# minutka_hlavni.net
KiCad netlist of a schematic drawn in EAGLE
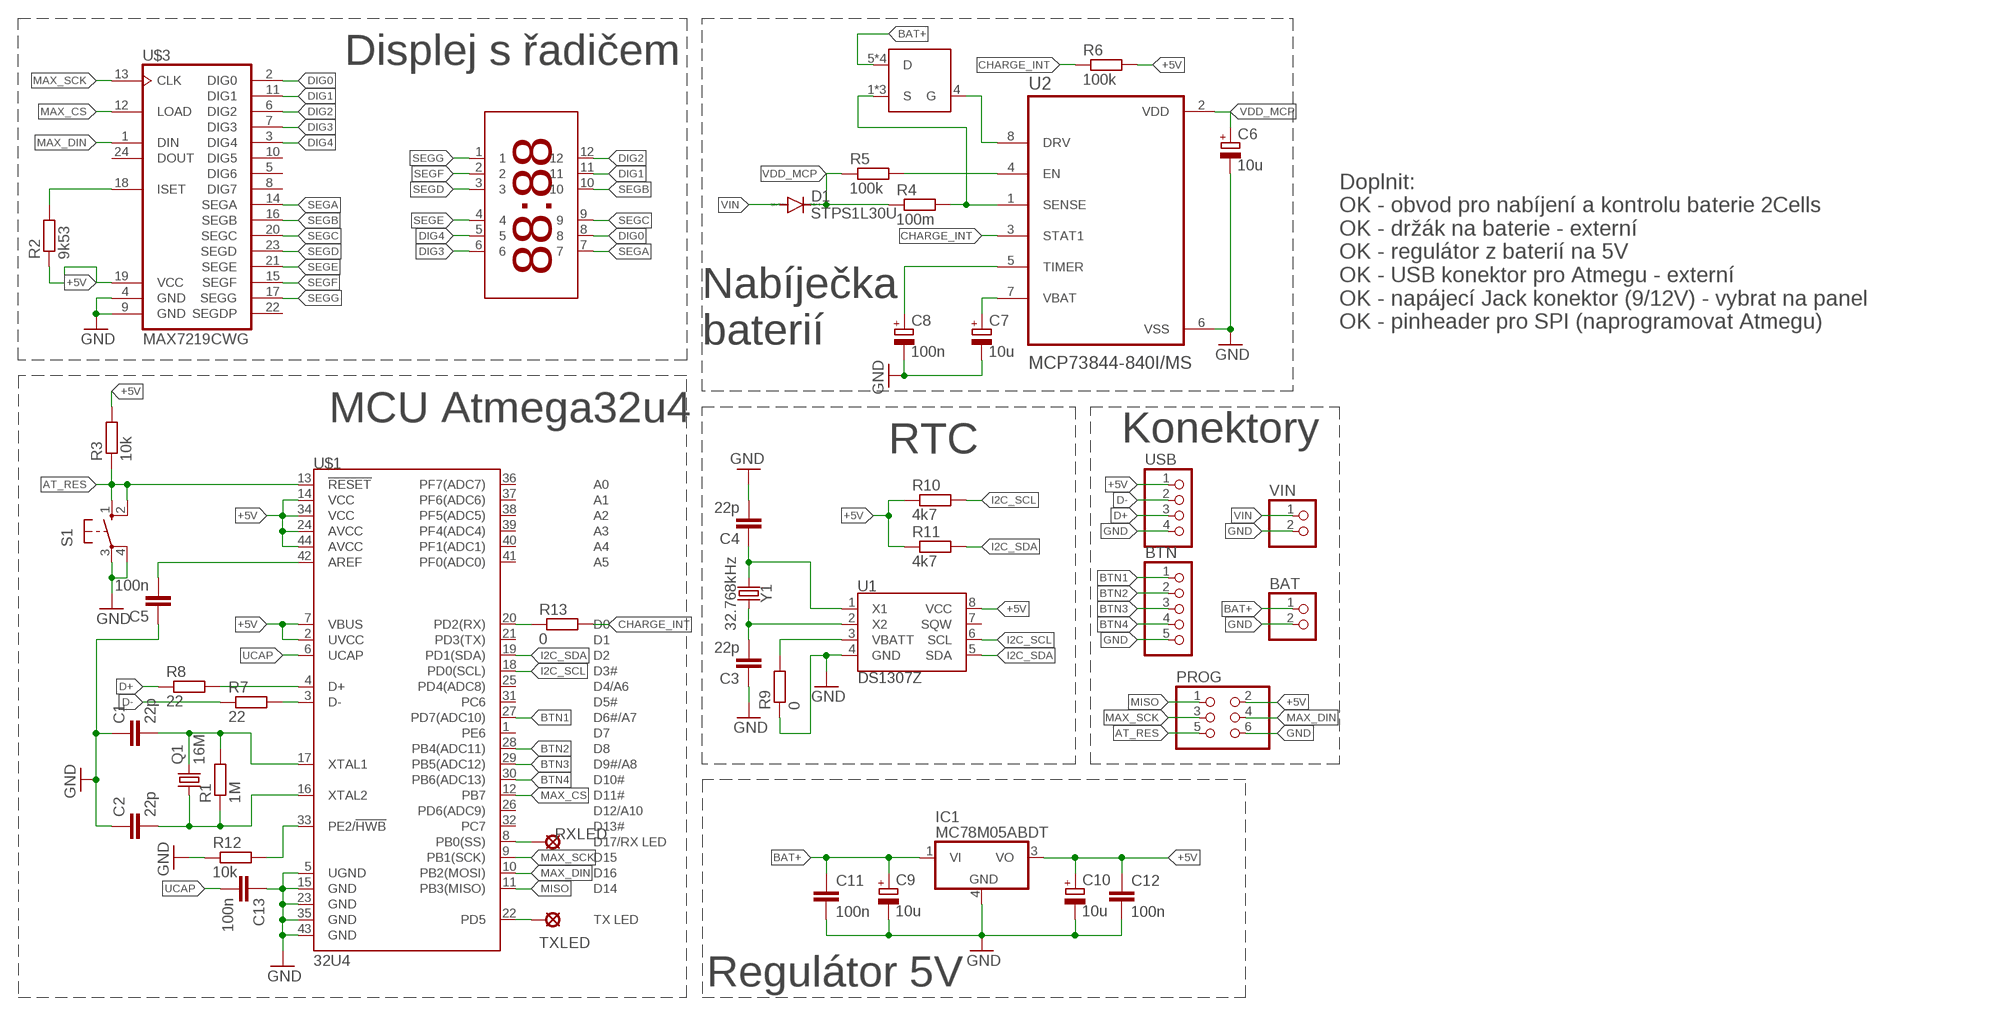
[diagram p0: schematic, sheet 1]

(export (version "E")
  (design (tool "Eeschema 10.0.6"))
  (components
    (comp (ref "BAT")
      (value "PINHD-1X2")
      (footprint "eagle-import:1X02")
      (libsource (lib "eagle-import") (part "PINHD-1X2"))
    )
    (comp (ref "BTN")
      (value "PINHD-1X5")
      (footprint "eagle-import:1X05")
      (libsource (lib "eagle-import") (part "PINHD-1X5"))
    )
    (comp (ref "C1")
      (value "22p")
      (footprint "eagle-import:C0603")
      (libsource (lib "eagle-import") (part "C-EUC0603"))
    )
    (comp (ref "C2")
      (value "22p")
      (footprint "eagle-import:C0603")
      (libsource (lib "eagle-import") (part "C-EUC0603"))
    )
    (comp (ref "C3")
      (value "22p")
      (footprint "eagle-import:C0603")
      (libsource (lib "eagle-import") (part "C-EUC0603"))
    )
    (comp (ref "C4")
      (value "22p")
      (footprint "eagle-import:C0603")
      (libsource (lib "eagle-import") (part "C-EUC0603"))
    )
    (comp (ref "C5")
      (value "100n")
      (footprint "eagle-import:C0603")
      (libsource (lib "eagle-import") (part "C-EUC0603"))
    )
    (comp (ref "C6")
      (value "10u")
      (footprint "eagle-import:085CS_1AR")
      (libsource (lib "eagle-import") (part "CPOL-EU085CS-1AR"))
    )
    (comp (ref "C7")
      (value "10u")
      (footprint "eagle-import:085CS_1AR")
      (libsource (lib "eagle-import") (part "CPOL-EU085CS-1AR"))
    )
    (comp (ref "C8")
      (value "100n")
      (footprint "eagle-import:085CS_1AR")
      (libsource (lib "eagle-import") (part "CPOL-EU085CS-1AR"))
    )
    (comp (ref "C9")
      (value "10u")
      (footprint "eagle-import:085CS_1AR")
      (libsource (lib "eagle-import") (part "CPOL-EU085CS-1AR"))
    )
    (comp (ref "C10")
      (value "10u")
      (footprint "eagle-import:085CS_1AR")
      (libsource (lib "eagle-import") (part "CPOL-EU085CS-1AR"))
    )
    (comp (ref "C11")
      (value "100n")
      (footprint "eagle-import:C0603")
      (libsource (lib "eagle-import") (part "C-EUC0603"))
    )
    (comp (ref "C12")
      (value "100n")
      (footprint "eagle-import:C0603")
      (libsource (lib "eagle-import") (part "C-EUC0603"))
    )
    (comp (ref "C13")
      (value "100n")
      (footprint "eagle-import:C0603")
      (libsource (lib "eagle-import") (part "C-EUC0603"))
    )
    (comp (ref "D1")
      (value "STPS1L30U")
      (footprint "eagle-import:DO214AA")
      (libsource (lib "eagle-import") (part "DIODE-DO214AA"))
    )
    (comp (ref "IC1")
      (value "MC78M05ABDT")
      (footprint "eagle-import:DPACK_3")
      (libsource (lib "eagle-import") (part "MC78M05ABDT"))
    )
    (comp (ref "PROG")
      (value "PINHD-2X3")
      (footprint "eagle-import:2X03")
      (libsource (lib "eagle-import") (part "PINHD-2X3"))
    )
    (comp (ref "Q1")
      (value "16M")
      (footprint "eagle-import:HC49UP")
      (libsource (lib "eagle-import") (part "CRYSTALHC49UP"))
    )
    (comp (ref "R1")
      (value "1M")
      (footprint "eagle-import:R0603")
      (libsource (lib "eagle-import") (part "R-EU_R0603"))
    )
    (comp (ref "R2")
      (value "9k53")
      (footprint "eagle-import:R0603")
      (libsource (lib "eagle-import") (part "R-EU_R0603"))
    )
    (comp (ref "R3")
      (value "10k")
      (footprint "eagle-import:R0603")
      (libsource (lib "eagle-import") (part "R-EU_R0603"))
    )
    (comp (ref "R4")
      (value "100m")
      (footprint "eagle-import:R0603")
      (libsource (lib "eagle-import") (part "R-EU_R0603"))
    )
    (comp (ref "R5")
      (value "100k")
      (footprint "eagle-import:R0603")
      (libsource (lib "eagle-import") (part "R-EU_R0603"))
    )
    (comp (ref "R6")
      (value "100k")
      (footprint "eagle-import:R0603")
      (libsource (lib "eagle-import") (part "R-EU_R0603"))
    )
    (comp (ref "R7")
      (value "22")
      (footprint "eagle-import:R0603")
      (libsource (lib "eagle-import") (part "R-EU_R0603"))
    )
    (comp (ref "R8")
      (value "22")
      (footprint "eagle-import:R0603")
      (libsource (lib "eagle-import") (part "R-EU_R0603"))
    )
    (comp (ref "R9")
      (value "0")
      (footprint "eagle-import:R0603")
      (libsource (lib "eagle-import") (part "R-EU_R0603"))
    )
    (comp (ref "R10")
      (value "4k7")
      (footprint "eagle-import:R0603")
      (libsource (lib "eagle-import") (part "R-EU_R0603"))
    )
    (comp (ref "R11")
      (value "4k7")
      (footprint "eagle-import:R0603")
      (libsource (lib "eagle-import") (part "R-EU_R0603"))
    )
    (comp (ref "R12")
      (value "10k")
      (footprint "eagle-import:R0603")
      (libsource (lib "eagle-import") (part "R-EU_R0603"))
    )
    (comp (ref "R13")
      (value "0")
      (footprint "eagle-import:R0603")
      (libsource (lib "eagle-import") (part "R-EU_R0603"))
    )
    (comp (ref "RXLED")
      (value "LSP13")
      (footprint "eagle-import:LSP13")
      (libsource (lib "eagle-import") (part "LSP13"))
    )
    (comp (ref "S1")
      (value "10-XX")
      (footprint "eagle-import:B3F-10XX")
      (fields (field (name "MPN") "B3F-1000"))
      (libsource (lib "eagle-import") (part "10-XX"))
    )
    (comp (ref "TXLED")
      (value "LSP13")
      (footprint "eagle-import:LSP13")
      (libsource (lib "eagle-import") (part "LSP13"))
    )
    (comp (ref "U$1")
      (value "32U4")
      (footprint "eagle-import:TQFP44")
      (libsource (lib "eagle-import") (part "ATMEGA32U4TQFP-44"))
    )
    (comp (ref "U$2")
      (value "KW4-8828AVB")
      (footprint "eagle-import:KW4-8828AVB")
      (libsource (lib "eagle-import") (part "KW4-8828AVB"))
    )
    (comp (ref "U$3")
      (value "MAX7219CWG")
      (footprint "eagle-import:SO24L")
      (libsource (lib "eagle-import") (part "MAX7219CWG"))
    )
    (comp (ref "U$4")
      (value "NDS8434")
      (footprint "eagle-import:SO08")
      (fields (field (name "MF") "ON Semiconductor / Fairchild"))
      (libsource (lib "eagle-import") (part "NDS8434"))
    )
    (comp (ref "U1")
      (value "DS1307Z")
      (footprint "eagle-import:SO08-0.15")
      (libsource (lib "eagle-import") (part "DS1307Z"))
    )
    (comp (ref "U2")
      (value "MCP73844-840I/MS")
      (footprint "eagle-import:SOP65P490X110-8N")
      (fields (field (name "MF") "Microchip"))
      (libsource (lib "eagle-import") (part "MCP73844-840I/MS"))
    )
    (comp (ref "USB")
      (value "PINHD-1X4")
      (footprint "eagle-import:1X04")
      (libsource (lib "eagle-import") (part "PINHD-1X4"))
    )
    (comp (ref "VIN")
      (value "PINHD-1X2")
      (footprint "eagle-import:1X02")
      (libsource (lib "eagle-import") (part "PINHD-1X2"))
    )
    (comp (ref "Y1")
      (value "32.768kHz")
      (footprint "eagle-import:CRYSTAL-SMD-2X6-CYL")
      (libsource (lib "eagle-import") (part "CRYSTAL-32.768KHZSMD-2X6"))
    )
  )
  (nets
    (net (code "1") (name "+5V") (class "Default")
      (node (ref "C10") (pin "+") (pinfunction "+_+") (pintype "passive"))
      (node (ref "C12") (pin "1") (pinfunction "1_1") (pintype "passive"))
      (node (ref "IC1") (pin "3") (pinfunction "VO_3") (pintype "passive"))
      (node (ref "PROG") (pin "2") (pinfunction "2_2") (pintype "passive"))
      (node (ref "R10") (pin "1") (pinfunction "1_1") (pintype "passive"))
      (node (ref "R11") (pin "1") (pinfunction "1_1") (pintype "passive"))
      (node (ref "R2") (pin "1") (pinfunction "1_1") (pintype "passive"))
      (node (ref "R3") (pin "2") (pinfunction "2_2") (pintype "passive"))
      (node (ref "R6") (pin "2") (pinfunction "2_2") (pintype "passive"))
      (node (ref "U$1") (pin "14") (pinfunction "VCC_14") (pintype "bidirectional"))
      (node (ref "U$1") (pin "2") (pinfunction "UVCC_2") (pintype "bidirectional"))
      (node (ref "U$1") (pin "24") (pinfunction "AVCC_24") (pintype "bidirectional"))
      (node (ref "U$1") (pin "34") (pinfunction "VCC_34") (pintype "bidirectional"))
      (node (ref "U$1") (pin "44") (pinfunction "AVCC_44") (pintype "bidirectional"))
      (node (ref "U$1") (pin "7") (pinfunction "VBUS_7") (pintype "bidirectional"))
      (node (ref "U$3") (pin "19") (pinfunction "VCC_19") (pintype "power_in"))
      (node (ref "U1") (pin "8") (pinfunction "VCC_8") (pintype "bidirectional"))
      (node (ref "USB") (pin "1") (pinfunction "1_1") (pintype "passive"))
    )
    (net (code "2") (name "AT_RES") (class "Default")
      (node (ref "PROG") (pin "5") (pinfunction "5_5") (pintype "passive"))
      (node (ref "R3") (pin "1") (pinfunction "1_1") (pintype "passive"))
      (node (ref "S1") (pin "1") (pinfunction "S_1") (pintype "passive"))
      (node (ref "S1") (pin "2") (pinfunction "S1_2") (pintype "passive"))
      (node (ref "U$1") (pin "13") (pinfunction "~{RESET}_13") (pintype "bidirectional"))
    )
    (net (code "3") (name "BAT+") (class "Default")
      (node (ref "BAT") (pin "1") (pinfunction "1_1") (pintype "passive"))
      (node (ref "C11") (pin "1") (pinfunction "1_1") (pintype "passive"))
      (node (ref "C9") (pin "+") (pinfunction "+_+") (pintype "passive"))
      (node (ref "IC1") (pin "1") (pinfunction "VI_1") (pintype "input"))
      (node (ref "U$4") (pin "5") (pinfunction "D_5") (pintype "bidirectional"))
      (node (ref "U$4") (pin "6") (pinfunction "D_6") (pintype "bidirectional"))
      (node (ref "U$4") (pin "7") (pinfunction "D_7") (pintype "bidirectional"))
      (node (ref "U$4") (pin "8") (pinfunction "D_8") (pintype "bidirectional"))
    )
    (net (code "4") (name "BTN1") (class "Default")
      (node (ref "BTN") (pin "1") (pinfunction "1_1") (pintype "passive"))
      (node (ref "U$1") (pin "27") (pinfunction "PD7(ADC10)_27") (pintype "bidirectional"))
    )
    (net (code "5") (name "BTN2") (class "Default")
      (node (ref "BTN") (pin "2") (pinfunction "2_2") (pintype "passive"))
      (node (ref "U$1") (pin "28") (pinfunction "PB4(ADC11)_28") (pintype "bidirectional"))
    )
    (net (code "6") (name "BTN3") (class "Default")
      (node (ref "BTN") (pin "3") (pinfunction "3_3") (pintype "passive"))
      (node (ref "U$1") (pin "29") (pinfunction "PB5(ADC12)_29") (pintype "bidirectional"))
    )
    (net (code "7") (name "BTN4") (class "Default")
      (node (ref "BTN") (pin "4") (pinfunction "4_4") (pintype "passive"))
      (node (ref "U$1") (pin "30") (pinfunction "PB6(ADC13)_30") (pintype "bidirectional"))
    )
    (net (code "8") (name "CHARGE_INT") (class "Default")
      (node (ref "R13") (pin "2") (pinfunction "2_2") (pintype "passive"))
      (node (ref "R6") (pin "1") (pinfunction "1_1") (pintype "passive"))
      (node (ref "U2") (pin "3") (pinfunction "STAT1_3") (pintype "bidirectional"))
    )
    (net (code "9") (name "D+") (class "Default")
      (node (ref "R8") (pin "1") (pinfunction "1_1") (pintype "passive"))
      (node (ref "USB") (pin "3") (pinfunction "3_3") (pintype "passive"))
    )
    (net (code "10") (name "D-") (class "Default")
      (node (ref "R7") (pin "1") (pinfunction "1_1") (pintype "passive"))
      (node (ref "USB") (pin "2") (pinfunction "2_2") (pintype "passive"))
    )
    (net (code "11") (name "DIG0") (class "Default")
      (node (ref "U$2") (pin "8") (pinfunction "8_8") (pintype "bidirectional"))
      (node (ref "U$3") (pin "2") (pinfunction "DIG0_2") (pintype "output"))
    )
    (net (code "12") (name "DIG1") (class "Default")
      (node (ref "U$2") (pin "11") (pinfunction "11_11") (pintype "bidirectional"))
      (node (ref "U$3") (pin "11") (pinfunction "DIG1_11") (pintype "output"))
    )
    (net (code "13") (name "DIG2") (class "Default")
      (node (ref "U$2") (pin "12") (pinfunction "12_12") (pintype "bidirectional"))
      (node (ref "U$3") (pin "6") (pinfunction "DIG2_6") (pintype "output"))
    )
    (net (code "14") (name "DIG3") (class "Default")
      (node (ref "U$2") (pin "6") (pinfunction "6_6") (pintype "bidirectional"))
      (node (ref "U$3") (pin "7") (pinfunction "DIG3_7") (pintype "output"))
    )
    (net (code "15") (name "DIG4") (class "Default")
      (node (ref "U$2") (pin "5") (pinfunction "5_5") (pintype "bidirectional"))
      (node (ref "U$3") (pin "3") (pinfunction "DIG4_3") (pintype "output"))
    )
    (net (code "16") (name "GND") (class "Default")
      (node (ref "BAT") (pin "2") (pinfunction "2_2") (pintype "passive"))
      (node (ref "BTN") (pin "5") (pinfunction "5_5") (pintype "passive"))
      (node (ref "C1") (pin "1") (pinfunction "1_1") (pintype "passive"))
      (node (ref "C10") (pin "-") (pinfunction "-_-") (pintype "passive"))
      (node (ref "C11") (pin "2") (pinfunction "2_2") (pintype "passive"))
      (node (ref "C12") (pin "2") (pinfunction "2_2") (pintype "passive"))
      (node (ref "C13") (pin "1") (pinfunction "1_1") (pintype "passive"))
      (node (ref "C2") (pin "1") (pinfunction "1_1") (pintype "passive"))
      (node (ref "C3") (pin "1") (pinfunction "1_1") (pintype "passive"))
      (node (ref "C4") (pin "2") (pinfunction "2_2") (pintype "passive"))
      (node (ref "C5") (pin "1") (pinfunction "1_1") (pintype "passive"))
      (node (ref "C6") (pin "-") (pinfunction "-_-") (pintype "passive"))
      (node (ref "C7") (pin "-") (pinfunction "-_-") (pintype "passive"))
      (node (ref "C8") (pin "-") (pinfunction "-_-") (pintype "passive"))
      (node (ref "C9") (pin "-") (pinfunction "-_-") (pintype "passive"))
      (node (ref "IC1") (pin "4") (pinfunction "GND_4") (pintype "passive"))
      (node (ref "PROG") (pin "6") (pinfunction "6_6") (pintype "passive"))
      (node (ref "R12") (pin "1") (pinfunction "1_1") (pintype "passive"))
      (node (ref "R9") (pin "1") (pinfunction "1_1") (pintype "passive"))
      (node (ref "S1") (pin "3") (pinfunction "P_3") (pintype "passive"))
      (node (ref "S1") (pin "4") (pinfunction "P1_4") (pintype "passive"))
      (node (ref "U$1") (pin "15") (pinfunction "GND_15") (pintype "bidirectional"))
      (node (ref "U$1") (pin "23") (pinfunction "GND_23") (pintype "bidirectional"))
      (node (ref "U$1") (pin "35") (pinfunction "GND_35") (pintype "bidirectional"))
      (node (ref "U$1") (pin "43") (pinfunction "GND_43") (pintype "bidirectional"))
      (node (ref "U$1") (pin "5") (pinfunction "UGND_5") (pintype "bidirectional"))
      (node (ref "U$3") (pin "4") (pinfunction "GND_4") (pintype "power_in"))
      (node (ref "U$3") (pin "9") (pinfunction "GND_9") (pintype "power_in"))
      (node (ref "U1") (pin "4") (pinfunction "GND_4") (pintype "bidirectional"))
      (node (ref "U2") (pin "6") (pinfunction "VSS_6") (pintype "power_in"))
      (node (ref "USB") (pin "4") (pinfunction "4_4") (pintype "passive"))
      (node (ref "VIN") (pin "2") (pinfunction "2_2") (pintype "passive"))
    )
    (net (code "17") (name "I2C_SCL") (class "Default")
      (node (ref "R10") (pin "2") (pinfunction "2_2") (pintype "passive"))
      (node (ref "U$1") (pin "18") (pinfunction "PD0(SCL)_18") (pintype "bidirectional"))
      (node (ref "U1") (pin "6") (pinfunction "SCL_6") (pintype "bidirectional"))
    )
    (net (code "18") (name "I2C_SDA") (class "Default")
      (node (ref "R11") (pin "2") (pinfunction "2_2") (pintype "passive"))
      (node (ref "U$1") (pin "19") (pinfunction "PD1(SDA)_19") (pintype "bidirectional"))
      (node (ref "U1") (pin "5") (pinfunction "SDA_5") (pintype "bidirectional"))
    )
    (net (code "19") (name "MAX_CS") (class "Default")
      (node (ref "U$1") (pin "12") (pinfunction "PB7_12") (pintype "bidirectional"))
      (node (ref "U$3") (pin "12") (pinfunction "LOAD_12") (pintype "input"))
    )
    (net (code "20") (name "MAX_DIN") (class "Default")
      (node (ref "PROG") (pin "4") (pinfunction "4_4") (pintype "passive"))
      (node (ref "U$1") (pin "10") (pinfunction "PB2(MOSI)_10") (pintype "bidirectional"))
      (node (ref "U$3") (pin "1") (pinfunction "DIN_1") (pintype "input"))
    )
    (net (code "21") (name "MAX_SCK") (class "Default")
      (node (ref "PROG") (pin "3") (pinfunction "3_3") (pintype "passive"))
      (node (ref "U$1") (pin "9") (pinfunction "PB1(SCK)_9") (pintype "bidirectional"))
      (node (ref "U$3") (pin "13") (pinfunction "CLK_13") (pintype "input"))
    )
    (net (code "22") (name "MISO") (class "Default")
      (node (ref "PROG") (pin "1") (pinfunction "1_1") (pintype "passive"))
      (node (ref "U$1") (pin "11") (pinfunction "PB3(MISO)_11") (pintype "bidirectional"))
    )
    (net (code "23") (name "Net-(U$1-AREF)") (class "Default")
      (node (ref "C5") (pin "2") (pinfunction "2_2") (pintype "passive"))
      (node (ref "U$1") (pin "42") (pinfunction "AREF_42") (pintype "bidirectional"))
    )
    (net (code "24") (name "Net-(U$1-D+)") (class "Default")
      (node (ref "R8") (pin "2") (pinfunction "2_2") (pintype "passive"))
      (node (ref "U$1") (pin "4") (pinfunction "D+_4") (pintype "bidirectional"))
    )
    (net (code "25") (name "Net-(U$1-D-)") (class "Default")
      (node (ref "R7") (pin "2") (pinfunction "2_2") (pintype "passive"))
      (node (ref "U$1") (pin "3") (pinfunction "D-_3") (pintype "bidirectional"))
    )
    (net (code "26") (name "Net-(U$1-PB0(SS))") (class "Default")
      (node (ref "RXLED") (pin "MP") (pinfunction "MP_MP") (pintype "passive"))
      (node (ref "U$1") (pin "8") (pinfunction "PB0(SS)_8") (pintype "bidirectional"))
    )
    (net (code "27") (name "Net-(U$1-PD2(RX))") (class "Default")
      (node (ref "R13") (pin "1") (pinfunction "1_1") (pintype "passive"))
      (node (ref "U$1") (pin "20") (pinfunction "PD2(RX)_20") (pintype "bidirectional"))
    )
    (net (code "28") (name "Net-(U$1-PD5)") (class "Default")
      (node (ref "TXLED") (pin "MP") (pinfunction "MP_MP") (pintype "passive"))
      (node (ref "U$1") (pin "22") (pinfunction "PD5_22") (pintype "bidirectional"))
    )
    (net (code "29") (name "Net-(U$1-PE2{slash}~{HWB})") (class "Default")
      (node (ref "R12") (pin "2") (pinfunction "2_2") (pintype "passive"))
      (node (ref "U$1") (pin "33") (pinfunction "PE2/~{HWB}_33") (pintype "bidirectional"))
    )
    (net (code "30") (name "Net-(U$1-XTAL1)") (class "Default")
      (node (ref "C1") (pin "2") (pinfunction "2_2") (pintype "passive"))
      (node (ref "Q1") (pin "2") (pinfunction "2_2") (pintype "passive"))
      (node (ref "R1") (pin "2") (pinfunction "2_2") (pintype "passive"))
      (node (ref "U$1") (pin "17") (pinfunction "XTAL1_17") (pintype "bidirectional"))
    )
    (net (code "31") (name "Net-(U$1-XTAL2)") (class "Default")
      (node (ref "C2") (pin "2") (pinfunction "2_2") (pintype "passive"))
      (node (ref "Q1") (pin "1") (pinfunction "1_1") (pintype "passive"))
      (node (ref "R1") (pin "1") (pinfunction "1_1") (pintype "passive"))
      (node (ref "U$1") (pin "16") (pinfunction "XTAL2_16") (pintype "bidirectional"))
    )
    (net (code "32") (name "Net-(U$3-ISET)") (class "Default")
      (node (ref "R2") (pin "2") (pinfunction "2_2") (pintype "passive"))
      (node (ref "U$3") (pin "18") (pinfunction "ISET_18") (pintype "input"))
    )
    (net (code "33") (name "Net-(U$4-G)") (class "Default")
      (node (ref "U$4") (pin "4") (pinfunction "G_4") (pintype "bidirectional"))
      (node (ref "U2") (pin "8") (pinfunction "DRV_8") (pintype "bidirectional"))
    )
    (net (code "34") (name "Net-(U1-VBATT)") (class "Default")
      (node (ref "R9") (pin "2") (pinfunction "2_2") (pintype "passive"))
      (node (ref "U1") (pin "3") (pinfunction "VBATT_3") (pintype "bidirectional"))
    )
    (net (code "35") (name "Net-(U1-X1)") (class "Default")
      (node (ref "C4") (pin "1") (pinfunction "1_1") (pintype "passive"))
      (node (ref "U1") (pin "1") (pinfunction "X1_1") (pintype "bidirectional"))
      (node (ref "Y1") (pin "X1") (pinfunction "1_X1") (pintype "passive"))
    )
    (net (code "36") (name "Net-(U1-X2)") (class "Default")
      (node (ref "C3") (pin "2") (pinfunction "2_2") (pintype "passive"))
      (node (ref "U1") (pin "2") (pinfunction "X2_2") (pintype "bidirectional"))
      (node (ref "Y1") (pin "X2") (pinfunction "2_X2") (pintype "passive"))
    )
    (net (code "37") (name "Net-(U2-EN)") (class "Default")
      (node (ref "R5") (pin "2") (pinfunction "2_2") (pintype "passive"))
      (node (ref "U2") (pin "4") (pinfunction "EN_4") (pintype "bidirectional"))
    )
    (net (code "38") (name "Net-(U2-SENSE)") (class "Default")
      (node (ref "R4") (pin "2") (pinfunction "2_2") (pintype "passive"))
      (node (ref "U$4") (pin "1") (pinfunction "S_1") (pintype "bidirectional"))
      (node (ref "U$4") (pin "2") (pinfunction "S_2") (pintype "bidirectional"))
      (node (ref "U$4") (pin "3") (pinfunction "S_3") (pintype "bidirectional"))
      (node (ref "U2") (pin "1") (pinfunction "SENSE_1") (pintype "bidirectional"))
    )
    (net (code "39") (name "Net-(U2-TIMER)") (class "Default")
      (node (ref "C8") (pin "+") (pinfunction "+_+") (pintype "passive"))
      (node (ref "U2") (pin "5") (pinfunction "TIMER_5") (pintype "bidirectional"))
    )
    (net (code "40") (name "Net-(U2-VBAT)") (class "Default")
      (node (ref "C7") (pin "+") (pinfunction "+_+") (pintype "passive"))
      (node (ref "U2") (pin "7") (pinfunction "VBAT_7") (pintype "bidirectional"))
    )
    (net (code "41") (name "SEGA") (class "Default")
      (node (ref "U$2") (pin "7") (pinfunction "7_7") (pintype "bidirectional"))
      (node (ref "U$3") (pin "14") (pinfunction "SEGA_14") (pintype "output"))
    )
    (net (code "42") (name "SEGB") (class "Default")
      (node (ref "U$2") (pin "10") (pinfunction "10_10") (pintype "bidirectional"))
      (node (ref "U$3") (pin "16") (pinfunction "SEGB_16") (pintype "output"))
    )
    (net (code "43") (name "SEGC") (class "Default")
      (node (ref "U$2") (pin "9") (pinfunction "9_9") (pintype "bidirectional"))
      (node (ref "U$3") (pin "20") (pinfunction "SEGC_20") (pintype "output"))
    )
    (net (code "44") (name "SEGD") (class "Default")
      (node (ref "U$2") (pin "3") (pinfunction "3_3") (pintype "bidirectional"))
      (node (ref "U$3") (pin "23") (pinfunction "SEGD_23") (pintype "output"))
    )
    (net (code "45") (name "SEGE") (class "Default")
      (node (ref "U$2") (pin "4") (pinfunction "4_4") (pintype "bidirectional"))
      (node (ref "U$3") (pin "21") (pinfunction "SEGE_21") (pintype "output"))
    )
    (net (code "46") (name "SEGF") (class "Default")
      (node (ref "U$2") (pin "2") (pinfunction "2_2") (pintype "bidirectional"))
      (node (ref "U$3") (pin "15") (pinfunction "SEGF_15") (pintype "output"))
    )
    (net (code "47") (name "SEGG") (class "Default")
      (node (ref "U$2") (pin "1") (pinfunction "1_1") (pintype "bidirectional"))
      (node (ref "U$3") (pin "17") (pinfunction "SEGG_17") (pintype "output"))
    )
    (net (code "48") (name "UCAP") (class "Default")
      (node (ref "C13") (pin "2") (pinfunction "2_2") (pintype "passive"))
      (node (ref "U$1") (pin "6") (pinfunction "UCAP_6") (pintype "bidirectional"))
    )
    (net (code "49") (name "VDD_MCP") (class "Default")
      (node (ref "C6") (pin "+") (pinfunction "+_+") (pintype "passive"))
      (node (ref "D1") (pin "C") (pinfunction "C_C") (pintype "passive"))
      (node (ref "R4") (pin "1") (pinfunction "1_1") (pintype "passive"))
      (node (ref "R5") (pin "1") (pinfunction "1_1") (pintype "passive"))
      (node (ref "U2") (pin "2") (pinfunction "VDD_2") (pintype "power_in"))
    )
    (net (code "50") (name "VIN") (class "Default")
      (node (ref "D1") (pin "A") (pinfunction "A_A") (pintype "passive"))
      (node (ref "VIN") (pin "1") (pinfunction "1_1") (pintype "passive"))
    )
    (net (code "51") (name "unconnected-(U$1-PC6-Pad31)") (class "Default")
      (node (ref "U$1") (pin "31") (pinfunction "PC6_31") (pintype "bidirectional"))
    )
    (net (code "52") (name "unconnected-(U$1-PC7-Pad32)") (class "Default")
      (node (ref "U$1") (pin "32") (pinfunction "PC7_32") (pintype "bidirectional"))
    )
    (net (code "53") (name "unconnected-(U$1-PD3(TX)-Pad21)") (class "Default")
      (node (ref "U$1") (pin "21") (pinfunction "PD3(TX)_21") (pintype "bidirectional"))
    )
    (net (code "54") (name "unconnected-(U$1-PD4(ADC8)-Pad25)") (class "Default")
      (node (ref "U$1") (pin "25") (pinfunction "PD4(ADC8)_25") (pintype "bidirectional"))
    )
    (net (code "55") (name "unconnected-(U$1-PD6(ADC9)-Pad26)") (class "Default")
      (node (ref "U$1") (pin "26") (pinfunction "PD6(ADC9)_26") (pintype "bidirectional"))
    )
    (net (code "56") (name "unconnected-(U$1-PE6-Pad1)") (class "Default")
      (node (ref "U$1") (pin "1") (pinfunction "PE6_1") (pintype "bidirectional"))
    )
    (net (code "57") (name "unconnected-(U$1-PF0(ADC0)-Pad41)") (class "Default")
      (node (ref "U$1") (pin "41") (pinfunction "PF0(ADC0)_41") (pintype "bidirectional"))
    )
    (net (code "58") (name "unconnected-(U$1-PF1(ADC1)-Pad40)") (class "Default")
      (node (ref "U$1") (pin "40") (pinfunction "PF1(ADC1)_40") (pintype "bidirectional"))
    )
    (net (code "59") (name "unconnected-(U$1-PF4(ADC4)-Pad39)") (class "Default")
      (node (ref "U$1") (pin "39") (pinfunction "PF4(ADC4)_39") (pintype "bidirectional"))
    )
    (net (code "60") (name "unconnected-(U$1-PF5(ADC5)-Pad38)") (class "Default")
      (node (ref "U$1") (pin "38") (pinfunction "PF5(ADC5)_38") (pintype "bidirectional"))
    )
    (net (code "61") (name "unconnected-(U$1-PF6(ADC6)-Pad37)") (class "Default")
      (node (ref "U$1") (pin "37") (pinfunction "PF6(ADC6)_37") (pintype "bidirectional"))
    )
    (net (code "62") (name "unconnected-(U$1-PF7(ADC7)-Pad36)") (class "Default")
      (node (ref "U$1") (pin "36") (pinfunction "PF7(ADC7)_36") (pintype "bidirectional"))
    )
    (net (code "63") (name "unconnected-(U$3-DIG5-Pad10)") (class "Default")
      (node (ref "U$3") (pin "10") (pinfunction "DIG5_10") (pintype "output"))
    )
    (net (code "64") (name "unconnected-(U$3-DIG6-Pad5)") (class "Default")
      (node (ref "U$3") (pin "5") (pinfunction "DIG6_5") (pintype "output"))
    )
    (net (code "65") (name "unconnected-(U$3-DIG7-Pad8)") (class "Default")
      (node (ref "U$3") (pin "8") (pinfunction "DIG7_8") (pintype "output"))
    )
    (net (code "66") (name "unconnected-(U$3-DOUT-Pad24)") (class "Default")
      (node (ref "U$3") (pin "24") (pinfunction "DOUT_24") (pintype "output"))
    )
    (net (code "67") (name "unconnected-(U$3-SEGDP-Pad22)") (class "Default")
      (node (ref "U$3") (pin "22") (pinfunction "SEGDP_22") (pintype "output"))
    )
    (net (code "68") (name "unconnected-(U1-SQW-Pad7)") (class "Default")
      (node (ref "U1") (pin "7") (pinfunction "SQW_7") (pintype "bidirectional"))
    )
  )
)
